# M304A.net
KiCad netlist of a schematic drawn in EAGLE
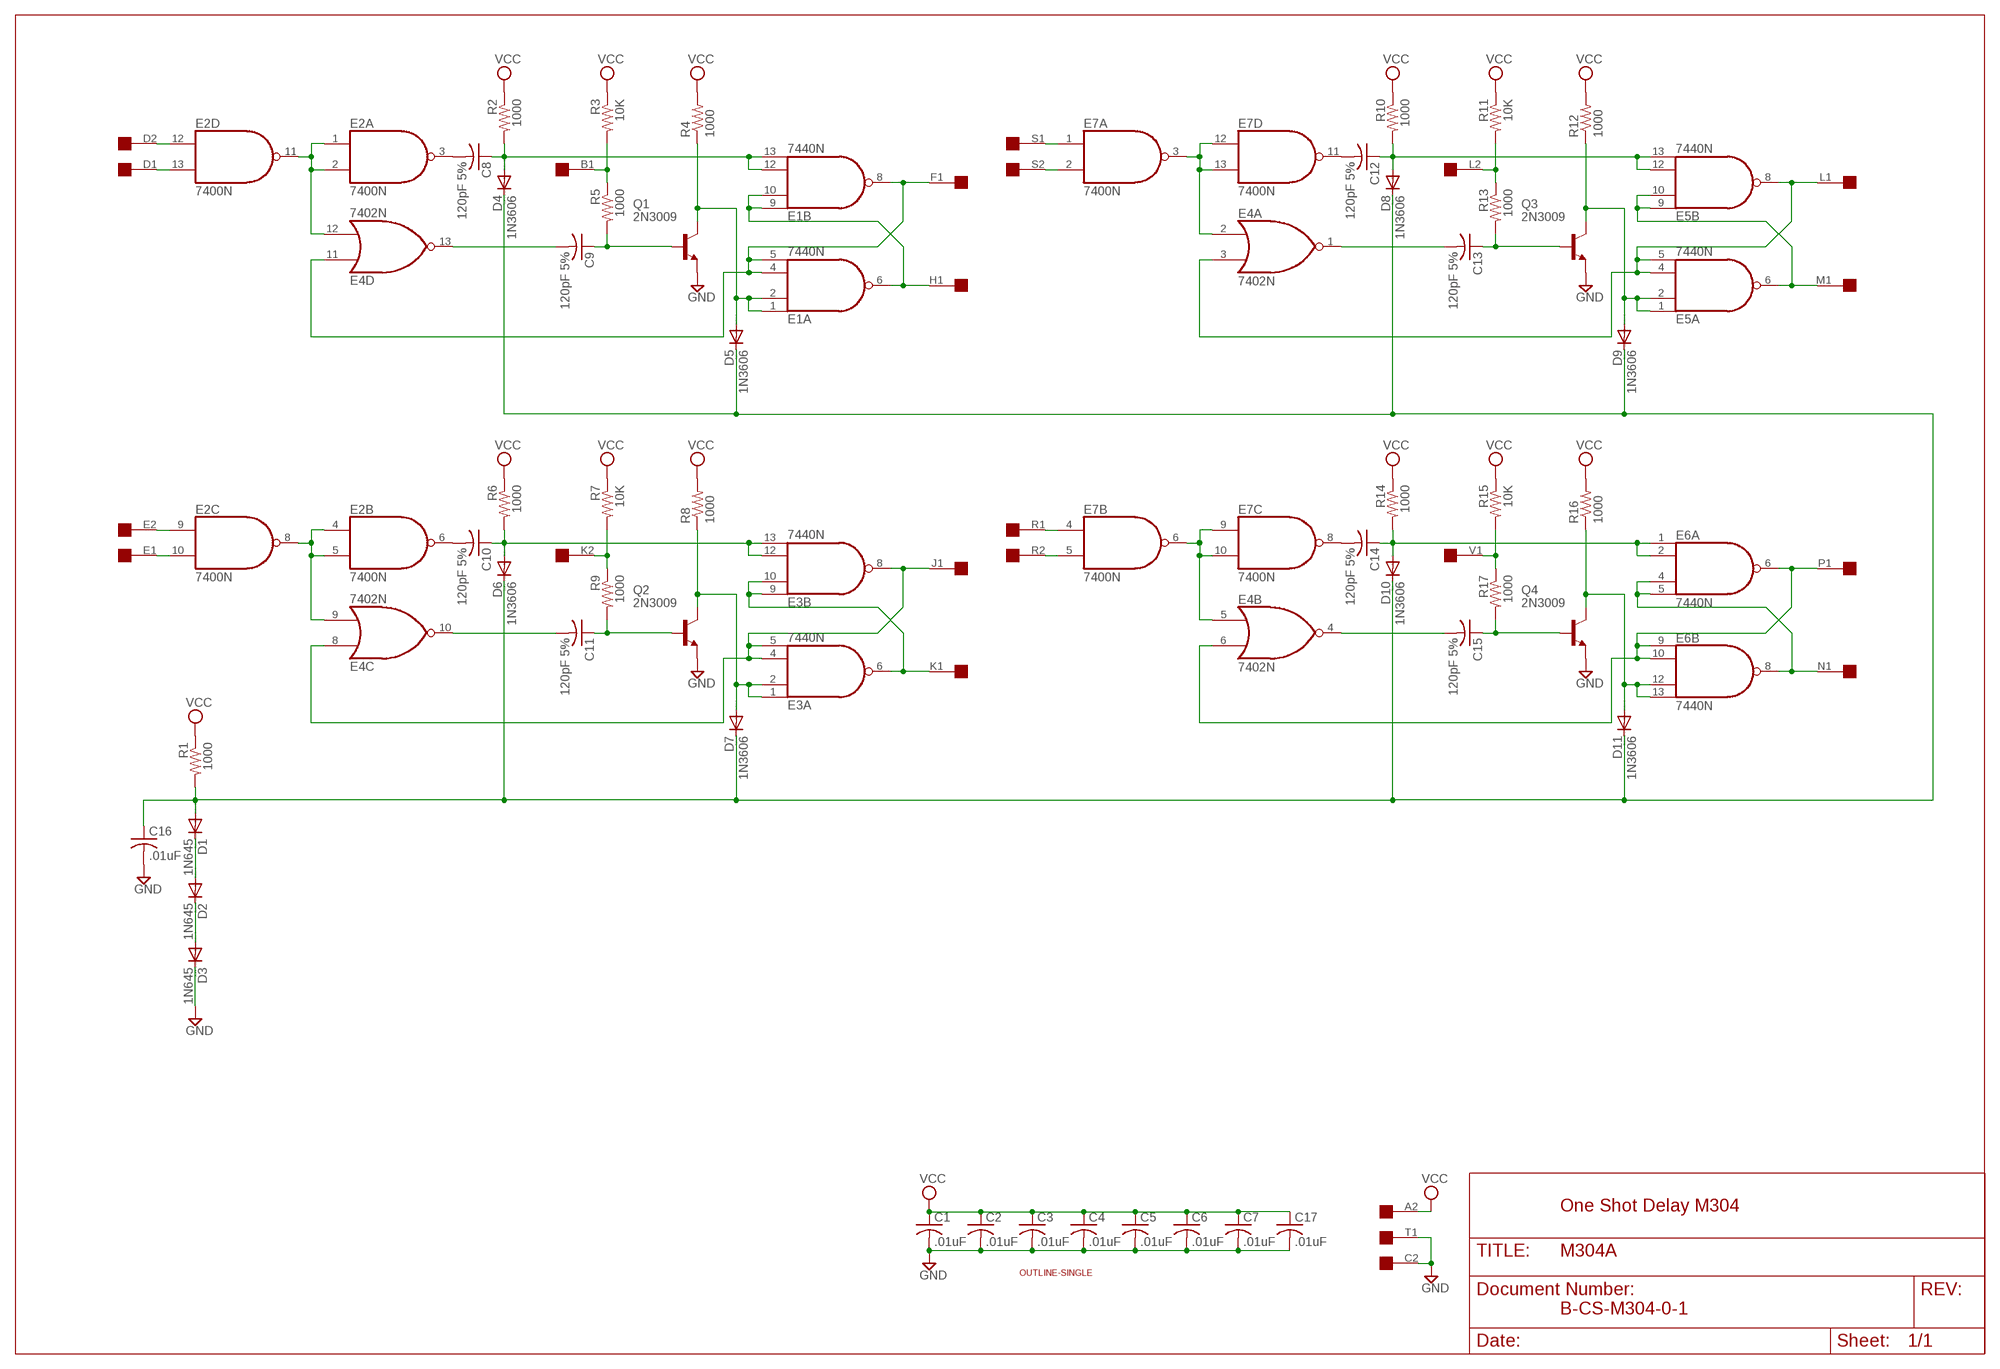
[diagram p0: schematic, sheet 1]

(export (version "E")
  (design (tool "Eeschema 10.0.6"))
  (components
    (comp (ref "C1")
      (value ".01uF")
      (footprint "eagle-import:C050-025X075")
      (libsource (lib "eagle-import") (part "C-US050-025X075"))
    )
    (comp (ref "C2")
      (value ".01uF")
      (footprint "eagle-import:C050-025X075")
      (libsource (lib "eagle-import") (part "C-US050-025X075"))
    )
    (comp (ref "C3")
      (value ".01uF")
      (footprint "eagle-import:C050-025X075")
      (libsource (lib "eagle-import") (part "C-US050-025X075"))
    )
    (comp (ref "C4")
      (value ".01uF")
      (footprint "eagle-import:C050-025X075")
      (libsource (lib "eagle-import") (part "C-US050-025X075"))
    )
    (comp (ref "C5")
      (value ".01uF")
      (footprint "eagle-import:C050-025X075")
      (libsource (lib "eagle-import") (part "C-US050-025X075"))
    )
    (comp (ref "C6")
      (value ".01uF")
      (footprint "eagle-import:C050-025X075")
      (libsource (lib "eagle-import") (part "C-US050-025X075"))
    )
    (comp (ref "C7")
      (value ".01uF")
      (footprint "eagle-import:C050-025X075")
      (libsource (lib "eagle-import") (part "C-US050-025X075"))
    )
    (comp (ref "C8")
      (value "120pF 5%")
      (footprint "eagle-import:C050-025X075")
      (libsource (lib "eagle-import") (part "C-US050-025X075"))
    )
    (comp (ref "C9")
      (value "120pF 5%")
      (footprint "eagle-import:C050-025X075")
      (libsource (lib "eagle-import") (part "C-US050-025X075"))
    )
    (comp (ref "C10")
      (value "120pF 5%")
      (footprint "eagle-import:C050-025X075")
      (libsource (lib "eagle-import") (part "C-US050-025X075"))
    )
    (comp (ref "C11")
      (value "120pF 5%")
      (footprint "eagle-import:C050-025X075")
      (libsource (lib "eagle-import") (part "C-US050-025X075"))
    )
    (comp (ref "C12")
      (value "120pF 5%")
      (footprint "eagle-import:C050-025X075")
      (libsource (lib "eagle-import") (part "C-US050-025X075"))
    )
    (comp (ref "C13")
      (value "120pF 5%")
      (footprint "eagle-import:C050-025X075")
      (libsource (lib "eagle-import") (part "C-US050-025X075"))
    )
    (comp (ref "C14")
      (value "120pF 5%")
      (footprint "eagle-import:C050-025X075")
      (libsource (lib "eagle-import") (part "C-US050-025X075"))
    )
    (comp (ref "C15")
      (value "120pF 5%")
      (footprint "eagle-import:C050-025X075")
      (libsource (lib "eagle-import") (part "C-US050-025X075"))
    )
    (comp (ref "C16")
      (value ".01uF")
      (footprint "eagle-import:C050-025X075")
      (libsource (lib "eagle-import") (part "C-US050-025X075"))
    )
    (comp (ref "C17")
      (value ".01uF")
      (footprint "eagle-import:C050-025X075")
      (libsource (lib "eagle-import") (part "C-US050-025X075"))
    )
    (comp (ref "D1")
      (value "1N645")
      (footprint "eagle-import:DO35-10")
      (libsource (lib "eagle-import") (part "1N4148DO35-10"))
    )
    (comp (ref "D2")
      (value "1N645")
      (footprint "eagle-import:DO35-10")
      (libsource (lib "eagle-import") (part "1N4148DO35-10"))
    )
    (comp (ref "D3")
      (value "1N645")
      (footprint "eagle-import:DO35-10")
      (libsource (lib "eagle-import") (part "1N4148DO35-10"))
    )
    (comp (ref "D4")
      (value "1N3606")
      (footprint "eagle-import:DO35-10")
      (libsource (lib "eagle-import") (part "1N4148DO35-10"))
    )
    (comp (ref "D5")
      (value "1N3606")
      (footprint "eagle-import:DO35-10")
      (libsource (lib "eagle-import") (part "1N4148DO35-10"))
    )
    (comp (ref "D6")
      (value "1N3606")
      (footprint "eagle-import:DO35-10")
      (libsource (lib "eagle-import") (part "1N4148DO35-10"))
    )
    (comp (ref "D7")
      (value "1N3606")
      (footprint "eagle-import:DO35-10")
      (libsource (lib "eagle-import") (part "1N4148DO35-10"))
    )
    (comp (ref "D8")
      (value "1N3606")
      (footprint "eagle-import:DO35-10")
      (libsource (lib "eagle-import") (part "1N4148DO35-10"))
    )
    (comp (ref "D9")
      (value "1N3606")
      (footprint "eagle-import:DO35-10")
      (libsource (lib "eagle-import") (part "1N4148DO35-10"))
    )
    (comp (ref "D10")
      (value "1N3606")
      (footprint "eagle-import:DO35-10")
      (libsource (lib "eagle-import") (part "1N4148DO35-10"))
    )
    (comp (ref "D11")
      (value "1N3606")
      (footprint "eagle-import:DO35-10")
      (libsource (lib "eagle-import") (part "1N4148DO35-10"))
    )
    (comp (ref "E1")
      (value "7440N")
      (footprint "eagle-import:DIL14")
      (libsource (lib "eagle-import") (part "7420NS"))
    )
    (comp (ref "E2")
      (value "7400N")
      (footprint "eagle-import:DIL14")
      (libsource (lib "eagle-import") (part "7400N"))
    )
    (comp (ref "E3")
      (value "7440N")
      (footprint "eagle-import:DIL14")
      (libsource (lib "eagle-import") (part "7420NS"))
    )
    (comp (ref "E4")
      (value "7402N")
      (footprint "eagle-import:DIL14")
      (libsource (lib "eagle-import") (part "7402N"))
    )
    (comp (ref "E5")
      (value "7440N")
      (footprint "eagle-import:DIL14")
      (libsource (lib "eagle-import") (part "7420NS"))
    )
    (comp (ref "E6")
      (value "7440N")
      (footprint "eagle-import:DIL14")
      (libsource (lib "eagle-import") (part "7420NS"))
    )
    (comp (ref "E7")
      (value "7400N")
      (footprint "eagle-import:DIL14")
      (libsource (lib "eagle-import") (part "7400N"))
    )
    (comp (ref "Q1")
      (value "2N3009")
      (footprint "eagle-import:TO39")
      (libsource (lib "eagle-import") (part "-NPN-TO39-EBC2N3019"))
    )
    (comp (ref "Q2")
      (value "2N3009")
      (footprint "eagle-import:TO39")
      (libsource (lib "eagle-import") (part "-NPN-TO39-EBC2N3019"))
    )
    (comp (ref "Q3")
      (value "2N3009")
      (footprint "eagle-import:TO39")
      (libsource (lib "eagle-import") (part "-NPN-TO39-EBC2N3019"))
    )
    (comp (ref "Q4")
      (value "2N3009")
      (footprint "eagle-import:TO39")
      (libsource (lib "eagle-import") (part "-NPN-TO39-EBC2N3019"))
    )
    (comp (ref "R1")
      (value "1000")
      (footprint "eagle-import:0207_10")
      (libsource (lib "eagle-import") (part "R-US_0207/10"))
    )
    (comp (ref "R2")
      (value "1000")
      (footprint "eagle-import:0207_10")
      (libsource (lib "eagle-import") (part "R-US_0207/10"))
    )
    (comp (ref "R3")
      (value "10K")
      (footprint "eagle-import:0207_10")
      (libsource (lib "eagle-import") (part "R-US_0207/10"))
    )
    (comp (ref "R4")
      (value "1000")
      (footprint "eagle-import:0207_10")
      (libsource (lib "eagle-import") (part "R-US_0207/10"))
    )
    (comp (ref "R5")
      (value "1000")
      (footprint "eagle-import:0207_10")
      (libsource (lib "eagle-import") (part "R-US_0207/10"))
    )
    (comp (ref "R6")
      (value "1000")
      (footprint "eagle-import:0207_10")
      (libsource (lib "eagle-import") (part "R-US_0207/10"))
    )
    (comp (ref "R7")
      (value "10K")
      (footprint "eagle-import:0207_10")
      (libsource (lib "eagle-import") (part "R-US_0207/10"))
    )
    (comp (ref "R8")
      (value "1000")
      (footprint "eagle-import:0207_10")
      (libsource (lib "eagle-import") (part "R-US_0207/10"))
    )
    (comp (ref "R9")
      (value "1000")
      (footprint "eagle-import:0207_10")
      (libsource (lib "eagle-import") (part "R-US_0207/10"))
    )
    (comp (ref "R10")
      (value "1000")
      (footprint "eagle-import:0207_10")
      (libsource (lib "eagle-import") (part "R-US_0207/10"))
    )
    (comp (ref "R11")
      (value "10K")
      (footprint "eagle-import:0207_10")
      (libsource (lib "eagle-import") (part "R-US_0207/10"))
    )
    (comp (ref "R12")
      (value "1000")
      (footprint "eagle-import:0207_10")
      (libsource (lib "eagle-import") (part "R-US_0207/10"))
    )
    (comp (ref "R13")
      (value "1000")
      (footprint "eagle-import:0207_10")
      (libsource (lib "eagle-import") (part "R-US_0207/10"))
    )
    (comp (ref "R14")
      (value "1000")
      (footprint "eagle-import:0207_10")
      (libsource (lib "eagle-import") (part "R-US_0207/10"))
    )
    (comp (ref "R15")
      (value "10K")
      (footprint "eagle-import:0207_10")
      (libsource (lib "eagle-import") (part "R-US_0207/10"))
    )
    (comp (ref "R16")
      (value "1000")
      (footprint "eagle-import:0207_10")
      (libsource (lib "eagle-import") (part "R-US_0207/10"))
    )
    (comp (ref "R17")
      (value "1000")
      (footprint "eagle-import:0207_10")
      (libsource (lib "eagle-import") (part "R-US_0207/10"))
    )
    (comp (ref "U$1")
      (value "SINGLE")
      (footprint "eagle-import:EDGE-CON2")
      (libsource (lib "eagle-import") (part "SINGLE"))
    )
    (comp (ref "U$2")
      (value "OUTLINE-SINGLE")
      (footprint "eagle-import:SINGLE")
      (libsource (lib "eagle-import") (part "OUTLINE-SINGLE"))
    )
  )
  (nets
    (net (code "1") (name "GND") (class "Default")
      (node (ref "C1") (pin "2") (pinfunction "2_2") (pintype "passive"))
      (node (ref "C16") (pin "2") (pinfunction "2_2") (pintype "passive"))
      (node (ref "C17") (pin "2") (pinfunction "2_2") (pintype "passive"))
      (node (ref "C2") (pin "2") (pinfunction "2_2") (pintype "passive"))
      (node (ref "C3") (pin "2") (pinfunction "2_2") (pintype "passive"))
      (node (ref "C4") (pin "2") (pinfunction "2_2") (pintype "passive"))
      (node (ref "C5") (pin "2") (pinfunction "2_2") (pintype "passive"))
      (node (ref "C6") (pin "2") (pinfunction "2_2") (pintype "passive"))
      (node (ref "C7") (pin "2") (pinfunction "2_2") (pintype "passive"))
      (node (ref "D3") (pin "C") (pinfunction "C_C") (pintype "passive"))
      (node (ref "Q1") (pin "1") (pinfunction "E_1") (pintype "passive"))
      (node (ref "Q2") (pin "1") (pinfunction "E_1") (pintype "passive"))
      (node (ref "Q3") (pin "1") (pinfunction "E_1") (pintype "passive"))
      (node (ref "Q4") (pin "1") (pinfunction "E_1") (pintype "passive"))
      (node (ref "U$1") (pin "C2") (pinfunction "1_C2") (pintype "bidirectional"))
      (node (ref "U$1") (pin "T1") (pinfunction "1_T1") (pintype "bidirectional"))
    )
    (net (code "2") (name "Net-(C16-Pad1)") (class "Default")
      (node (ref "C16") (pin "1") (pinfunction "1_1") (pintype "passive"))
      (node (ref "D1") (pin "A") (pinfunction "A_A") (pintype "passive"))
      (node (ref "D10") (pin "C") (pinfunction "C_C") (pintype "passive"))
      (node (ref "D11") (pin "C") (pinfunction "C_C") (pintype "passive"))
      (node (ref "D4") (pin "C") (pinfunction "C_C") (pintype "passive"))
      (node (ref "D5") (pin "C") (pinfunction "C_C") (pintype "passive"))
      (node (ref "D6") (pin "C") (pinfunction "C_C") (pintype "passive"))
      (node (ref "D7") (pin "C") (pinfunction "C_C") (pintype "passive"))
      (node (ref "D8") (pin "C") (pinfunction "C_C") (pintype "passive"))
      (node (ref "D9") (pin "C") (pinfunction "C_C") (pintype "passive"))
      (node (ref "R1") (pin "2") (pinfunction "2_2") (pintype "passive"))
    )
    (net (code "3") (name "Net-(D1-PadC)") (class "Default")
      (node (ref "D1") (pin "C") (pinfunction "C_C") (pintype "passive"))
      (node (ref "D2") (pin "A") (pinfunction "A_A") (pintype "passive"))
    )
    (net (code "4") (name "Net-(D2-PadC)") (class "Default")
      (node (ref "D2") (pin "C") (pinfunction "C_C") (pintype "passive"))
      (node (ref "D3") (pin "A") (pinfunction "A_A") (pintype "passive"))
    )
    (net (code "5") (name "Net-(E1A-I0)") (class "Default")
      (node (ref "D5") (pin "A") (pinfunction "A_A") (pintype "passive"))
      (node (ref "E1") (pin "1") (pinfunction "I0_1") (pintype "input"))
      (node (ref "E1") (pin "2") (pinfunction "I1_2") (pintype "input"))
      (node (ref "Q1") (pin "3") (pinfunction "C_3") (pintype "passive"))
      (node (ref "R4") (pin "1") (pinfunction "1_1") (pintype "passive"))
    )
    (net (code "6") (name "Net-(E1A-I2)") (class "Default")
      (node (ref "E1") (pin "4") (pinfunction "I2_4") (pintype "input"))
      (node (ref "E1") (pin "5") (pinfunction "I3_5") (pintype "input"))
      (node (ref "E1") (pin "8") (pinfunction "O_8") (pintype "output"))
      (node (ref "E4") (pin "11") (pinfunction "I0_11") (pintype "input"))
      (node (ref "U$1") (pin "F1") (pinfunction "1_F1") (pintype "bidirectional"))
    )
    (net (code "7") (name "Net-(E1A-O)") (class "Default")
      (node (ref "E1") (pin "10") (pinfunction "I1_10") (pintype "input"))
      (node (ref "E1") (pin "6") (pinfunction "O_6") (pintype "output"))
      (node (ref "E1") (pin "9") (pinfunction "I0_9") (pintype "input"))
      (node (ref "U$1") (pin "H1") (pinfunction "1_H1") (pintype "bidirectional"))
    )
    (net (code "8") (name "Net-(E1B-I2)") (class "Default")
      (node (ref "C8") (pin "1") (pinfunction "1_1") (pintype "passive"))
      (node (ref "D4") (pin "A") (pinfunction "A_A") (pintype "passive"))
      (node (ref "E1") (pin "12") (pinfunction "I2_12") (pintype "input"))
      (node (ref "E1") (pin "13") (pinfunction "I3_13") (pintype "input"))
      (node (ref "R2") (pin "2") (pinfunction "2_2") (pintype "passive"))
    )
    (net (code "9") (name "Net-(E2A-I0)") (class "Default")
      (node (ref "E2") (pin "1") (pinfunction "I0_1") (pintype "input"))
      (node (ref "E2") (pin "11") (pinfunction "O_11") (pintype "output"))
      (node (ref "E2") (pin "2") (pinfunction "I1_2") (pintype "input"))
      (node (ref "E4") (pin "12") (pinfunction "I1_12") (pintype "input"))
    )
    (net (code "10") (name "Net-(E2A-O)") (class "Default")
      (node (ref "C8") (pin "2") (pinfunction "2_2") (pintype "passive"))
      (node (ref "E2") (pin "3") (pinfunction "O_3") (pintype "output"))
    )
    (net (code "11") (name "Net-(E2B-I0)") (class "Default")
      (node (ref "E2") (pin "4") (pinfunction "I0_4") (pintype "input"))
      (node (ref "E2") (pin "5") (pinfunction "I1_5") (pintype "input"))
      (node (ref "E2") (pin "8") (pinfunction "O_8") (pintype "output"))
      (node (ref "E4") (pin "9") (pinfunction "I1_9") (pintype "input"))
    )
    (net (code "12") (name "Net-(E2B-O)") (class "Default")
      (node (ref "C10") (pin "2") (pinfunction "2_2") (pintype "passive"))
      (node (ref "E2") (pin "6") (pinfunction "O_6") (pintype "output"))
    )
    (net (code "13") (name "Net-(E2C-I0)") (class "Default")
      (node (ref "E2") (pin "9") (pinfunction "I0_9") (pintype "input"))
      (node (ref "U$1") (pin "E2") (pinfunction "1_E2") (pintype "bidirectional"))
    )
    (net (code "14") (name "Net-(E2C-I1)") (class "Default")
      (node (ref "E2") (pin "10") (pinfunction "I1_10") (pintype "input"))
      (node (ref "U$1") (pin "E1") (pinfunction "1_E1") (pintype "bidirectional"))
    )
    (net (code "15") (name "Net-(E2D-I0)") (class "Default")
      (node (ref "E2") (pin "12") (pinfunction "I0_12") (pintype "input"))
      (node (ref "U$1") (pin "D2") (pinfunction "1_D2") (pintype "bidirectional"))
    )
    (net (code "16") (name "Net-(E2D-I1)") (class "Default")
      (node (ref "E2") (pin "13") (pinfunction "I1_13") (pintype "input"))
      (node (ref "U$1") (pin "D1") (pinfunction "1_D1") (pintype "bidirectional"))
    )
    (net (code "17") (name "Net-(E3A-I0)") (class "Default")
      (node (ref "D7") (pin "A") (pinfunction "A_A") (pintype "passive"))
      (node (ref "E3") (pin "1") (pinfunction "I0_1") (pintype "input"))
      (node (ref "E3") (pin "2") (pinfunction "I1_2") (pintype "input"))
      (node (ref "Q2") (pin "3") (pinfunction "C_3") (pintype "passive"))
      (node (ref "R8") (pin "1") (pinfunction "1_1") (pintype "passive"))
    )
    (net (code "18") (name "Net-(E3A-I2)") (class "Default")
      (node (ref "E3") (pin "4") (pinfunction "I2_4") (pintype "input"))
      (node (ref "E3") (pin "5") (pinfunction "I3_5") (pintype "input"))
      (node (ref "E3") (pin "8") (pinfunction "O_8") (pintype "output"))
      (node (ref "E4") (pin "8") (pinfunction "I0_8") (pintype "input"))
      (node (ref "U$1") (pin "J1") (pinfunction "1_J1") (pintype "bidirectional"))
    )
    (net (code "19") (name "Net-(E3A-O)") (class "Default")
      (node (ref "E3") (pin "10") (pinfunction "I1_10") (pintype "input"))
      (node (ref "E3") (pin "6") (pinfunction "O_6") (pintype "output"))
      (node (ref "E3") (pin "9") (pinfunction "I0_9") (pintype "input"))
      (node (ref "U$1") (pin "K1") (pinfunction "1_K1") (pintype "bidirectional"))
    )
    (net (code "20") (name "Net-(E3B-I2)") (class "Default")
      (node (ref "C10") (pin "1") (pinfunction "1_1") (pintype "passive"))
      (node (ref "D6") (pin "A") (pinfunction "A_A") (pintype "passive"))
      (node (ref "E3") (pin "12") (pinfunction "I2_12") (pintype "input"))
      (node (ref "E3") (pin "13") (pinfunction "I3_13") (pintype "input"))
      (node (ref "R6") (pin "2") (pinfunction "2_2") (pintype "passive"))
    )
    (net (code "21") (name "Net-(E4A-I0)") (class "Default")
      (node (ref "E4") (pin "2") (pinfunction "I0_2") (pintype "input"))
      (node (ref "E7") (pin "12") (pinfunction "I0_12") (pintype "input"))
      (node (ref "E7") (pin "13") (pinfunction "I1_13") (pintype "input"))
      (node (ref "E7") (pin "3") (pinfunction "O_3") (pintype "output"))
    )
    (net (code "22") (name "Net-(E4A-I1)") (class "Default")
      (node (ref "E4") (pin "3") (pinfunction "I1_3") (pintype "input"))
      (node (ref "E5") (pin "4") (pinfunction "I2_4") (pintype "input"))
      (node (ref "E5") (pin "5") (pinfunction "I3_5") (pintype "input"))
      (node (ref "E5") (pin "8") (pinfunction "O_8") (pintype "output"))
      (node (ref "U$1") (pin "L1") (pinfunction "1_L1") (pintype "bidirectional"))
    )
    (net (code "23") (name "Net-(E4A-O)") (class "Default")
      (node (ref "C13") (pin "2") (pinfunction "2_2") (pintype "passive"))
      (node (ref "E4") (pin "1") (pinfunction "O_1") (pintype "output"))
    )
    (net (code "24") (name "Net-(E4B-I0)") (class "Default")
      (node (ref "E4") (pin "5") (pinfunction "I0_5") (pintype "input"))
      (node (ref "E7") (pin "10") (pinfunction "I1_10") (pintype "input"))
      (node (ref "E7") (pin "6") (pinfunction "O_6") (pintype "output"))
      (node (ref "E7") (pin "9") (pinfunction "I0_9") (pintype "input"))
    )
    (net (code "25") (name "Net-(E4B-I1)") (class "Default")
      (node (ref "E4") (pin "6") (pinfunction "I1_6") (pintype "input"))
      (node (ref "E6") (pin "10") (pinfunction "I1_10") (pintype "input"))
      (node (ref "E6") (pin "6") (pinfunction "O_6") (pintype "output"))
      (node (ref "E6") (pin "9") (pinfunction "I0_9") (pintype "input"))
      (node (ref "U$1") (pin "P1") (pinfunction "1_P1") (pintype "bidirectional"))
    )
    (net (code "26") (name "Net-(E4B-O)") (class "Default")
      (node (ref "C15") (pin "2") (pinfunction "2_2") (pintype "passive"))
      (node (ref "E4") (pin "4") (pinfunction "O_4") (pintype "output"))
    )
    (net (code "27") (name "Net-(E4C-O)") (class "Default")
      (node (ref "C11") (pin "2") (pinfunction "2_2") (pintype "passive"))
      (node (ref "E4") (pin "10") (pinfunction "O_10") (pintype "output"))
    )
    (net (code "28") (name "Net-(E4D-O)") (class "Default")
      (node (ref "C9") (pin "2") (pinfunction "2_2") (pintype "passive"))
      (node (ref "E4") (pin "13") (pinfunction "O_13") (pintype "output"))
    )
    (net (code "29") (name "Net-(E5A-I0)") (class "Default")
      (node (ref "D9") (pin "A") (pinfunction "A_A") (pintype "passive"))
      (node (ref "E5") (pin "1") (pinfunction "I0_1") (pintype "input"))
      (node (ref "E5") (pin "2") (pinfunction "I1_2") (pintype "input"))
      (node (ref "Q3") (pin "3") (pinfunction "C_3") (pintype "passive"))
      (node (ref "R12") (pin "1") (pinfunction "1_1") (pintype "passive"))
    )
    (net (code "30") (name "Net-(E5A-O)") (class "Default")
      (node (ref "E5") (pin "10") (pinfunction "I1_10") (pintype "input"))
      (node (ref "E5") (pin "6") (pinfunction "O_6") (pintype "output"))
      (node (ref "E5") (pin "9") (pinfunction "I0_9") (pintype "input"))
      (node (ref "U$1") (pin "M1") (pinfunction "1_M1") (pintype "bidirectional"))
    )
    (net (code "31") (name "Net-(E5B-I2)") (class "Default")
      (node (ref "C12") (pin "1") (pinfunction "1_1") (pintype "passive"))
      (node (ref "D8") (pin "A") (pinfunction "A_A") (pintype "passive"))
      (node (ref "E5") (pin "12") (pinfunction "I2_12") (pintype "input"))
      (node (ref "E5") (pin "13") (pinfunction "I3_13") (pintype "input"))
      (node (ref "R10") (pin "2") (pinfunction "2_2") (pintype "passive"))
    )
    (net (code "32") (name "Net-(E6A-I0)") (class "Default")
      (node (ref "C14") (pin "1") (pinfunction "1_1") (pintype "passive"))
      (node (ref "D10") (pin "A") (pinfunction "A_A") (pintype "passive"))
      (node (ref "E6") (pin "1") (pinfunction "I0_1") (pintype "input"))
      (node (ref "E6") (pin "2") (pinfunction "I1_2") (pintype "input"))
      (node (ref "R14") (pin "2") (pinfunction "2_2") (pintype "passive"))
    )
    (net (code "33") (name "Net-(E6A-I2)") (class "Default")
      (node (ref "E6") (pin "4") (pinfunction "I2_4") (pintype "input"))
      (node (ref "E6") (pin "5") (pinfunction "I3_5") (pintype "input"))
      (node (ref "E6") (pin "8") (pinfunction "O_8") (pintype "output"))
      (node (ref "U$1") (pin "N1") (pinfunction "1_N1") (pintype "bidirectional"))
    )
    (net (code "34") (name "Net-(E6B-I2)") (class "Default")
      (node (ref "D11") (pin "A") (pinfunction "A_A") (pintype "passive"))
      (node (ref "E6") (pin "12") (pinfunction "I2_12") (pintype "input"))
      (node (ref "E6") (pin "13") (pinfunction "I3_13") (pintype "input"))
      (node (ref "Q4") (pin "3") (pinfunction "C_3") (pintype "passive"))
      (node (ref "R16") (pin "1") (pinfunction "1_1") (pintype "passive"))
    )
    (net (code "35") (name "Net-(E7A-I0)") (class "Default")
      (node (ref "E7") (pin "1") (pinfunction "I0_1") (pintype "input"))
      (node (ref "U$1") (pin "S1") (pinfunction "1_S1") (pintype "bidirectional"))
    )
    (net (code "36") (name "Net-(E7A-I1)") (class "Default")
      (node (ref "E7") (pin "2") (pinfunction "I1_2") (pintype "input"))
      (node (ref "U$1") (pin "S2") (pinfunction "1_S2") (pintype "bidirectional"))
    )
    (net (code "37") (name "Net-(E7B-I0)") (class "Default")
      (node (ref "E7") (pin "4") (pinfunction "I0_4") (pintype "input"))
      (node (ref "U$1") (pin "R1") (pinfunction "1_R1") (pintype "bidirectional"))
    )
    (net (code "38") (name "Net-(E7B-I1)") (class "Default")
      (node (ref "E7") (pin "5") (pinfunction "I1_5") (pintype "input"))
      (node (ref "U$1") (pin "R2") (pinfunction "1_R2") (pintype "bidirectional"))
    )
    (net (code "39") (name "Net-(E7C-O)") (class "Default")
      (node (ref "C14") (pin "2") (pinfunction "2_2") (pintype "passive"))
      (node (ref "E7") (pin "8") (pinfunction "O_8") (pintype "output"))
    )
    (net (code "40") (name "Net-(E7D-O)") (class "Default")
      (node (ref "C12") (pin "2") (pinfunction "2_2") (pintype "passive"))
      (node (ref "E7") (pin "11") (pinfunction "O_11") (pintype "output"))
    )
    (net (code "41") (name "Net-(Q1-B)") (class "Default")
      (node (ref "C9") (pin "1") (pinfunction "1_1") (pintype "passive"))
      (node (ref "Q1") (pin "2") (pinfunction "B_2") (pintype "passive"))
      (node (ref "R5") (pin "2") (pinfunction "2_2") (pintype "passive"))
    )
    (net (code "42") (name "Net-(Q2-B)") (class "Default")
      (node (ref "C11") (pin "1") (pinfunction "1_1") (pintype "passive"))
      (node (ref "Q2") (pin "2") (pinfunction "B_2") (pintype "passive"))
      (node (ref "R9") (pin "2") (pinfunction "2_2") (pintype "passive"))
    )
    (net (code "43") (name "Net-(Q3-B)") (class "Default")
      (node (ref "C13") (pin "1") (pinfunction "1_1") (pintype "passive"))
      (node (ref "Q3") (pin "2") (pinfunction "B_2") (pintype "passive"))
      (node (ref "R13") (pin "2") (pinfunction "2_2") (pintype "passive"))
    )
    (net (code "44") (name "Net-(Q4-B)") (class "Default")
      (node (ref "C15") (pin "1") (pinfunction "1_1") (pintype "passive"))
      (node (ref "Q4") (pin "2") (pinfunction "B_2") (pintype "passive"))
      (node (ref "R17") (pin "2") (pinfunction "2_2") (pintype "passive"))
    )
    (net (code "45") (name "Net-(U$1AI-1)") (class "Default")
      (node (ref "R15") (pin "2") (pinfunction "2_2") (pintype "passive"))
      (node (ref "R17") (pin "1") (pinfunction "1_1") (pintype "passive"))
      (node (ref "U$1") (pin "V1") (pinfunction "1_V1") (pintype "bidirectional"))
    )
    (net (code "46") (name "Net-(U$1C-1)") (class "Default")
      (node (ref "R3") (pin "2") (pinfunction "2_2") (pintype "passive"))
      (node (ref "R5") (pin "1") (pinfunction "1_1") (pintype "passive"))
      (node (ref "U$1") (pin "B1") (pinfunction "1_B1") (pintype "bidirectional"))
    )
    (net (code "47") (name "Net-(U$1R-1)") (class "Default")
      (node (ref "R7") (pin "2") (pinfunction "2_2") (pintype "passive"))
      (node (ref "R9") (pin "1") (pinfunction "1_1") (pintype "passive"))
      (node (ref "U$1") (pin "K2") (pinfunction "1_K2") (pintype "bidirectional"))
    )
    (net (code "48") (name "Net-(U$1T-1)") (class "Default")
      (node (ref "R11") (pin "2") (pinfunction "2_2") (pintype "passive"))
      (node (ref "R13") (pin "1") (pinfunction "1_1") (pintype "passive"))
      (node (ref "U$1") (pin "L2") (pinfunction "1_L2") (pintype "bidirectional"))
    )
    (net (code "49") (name "VCC") (class "Default")
      (node (ref "C1") (pin "1") (pinfunction "1_1") (pintype "passive"))
      (node (ref "C17") (pin "1") (pinfunction "1_1") (pintype "passive"))
      (node (ref "C2") (pin "1") (pinfunction "1_1") (pintype "passive"))
      (node (ref "C3") (pin "1") (pinfunction "1_1") (pintype "passive"))
      (node (ref "C4") (pin "1") (pinfunction "1_1") (pintype "passive"))
      (node (ref "C5") (pin "1") (pinfunction "1_1") (pintype "passive"))
      (node (ref "C6") (pin "1") (pinfunction "1_1") (pintype "passive"))
      (node (ref "C7") (pin "1") (pinfunction "1_1") (pintype "passive"))
      (node (ref "R1") (pin "1") (pinfunction "1_1") (pintype "passive"))
      (node (ref "R10") (pin "1") (pinfunction "1_1") (pintype "passive"))
      (node (ref "R11") (pin "1") (pinfunction "1_1") (pintype "passive"))
      (node (ref "R12") (pin "2") (pinfunction "2_2") (pintype "passive"))
      (node (ref "R14") (pin "1") (pinfunction "1_1") (pintype "passive"))
      (node (ref "R15") (pin "1") (pinfunction "1_1") (pintype "passive"))
      (node (ref "R16") (pin "2") (pinfunction "2_2") (pintype "passive"))
      (node (ref "R2") (pin "1") (pinfunction "1_1") (pintype "passive"))
      (node (ref "R3") (pin "1") (pinfunction "1_1") (pintype "passive"))
      (node (ref "R4") (pin "2") (pinfunction "2_2") (pintype "passive"))
      (node (ref "R6") (pin "1") (pinfunction "1_1") (pintype "passive"))
      (node (ref "R7") (pin "1") (pinfunction "1_1") (pintype "passive"))
      (node (ref "R8") (pin "2") (pinfunction "2_2") (pintype "passive"))
      (node (ref "U$1") (pin "A2") (pinfunction "1_A2") (pintype "bidirectional"))
    )
  )
)
